# MCU_CLOCK_AND_USER_INTERFACE.net
KiCad netlist of a schematic drawn in Altium Designer
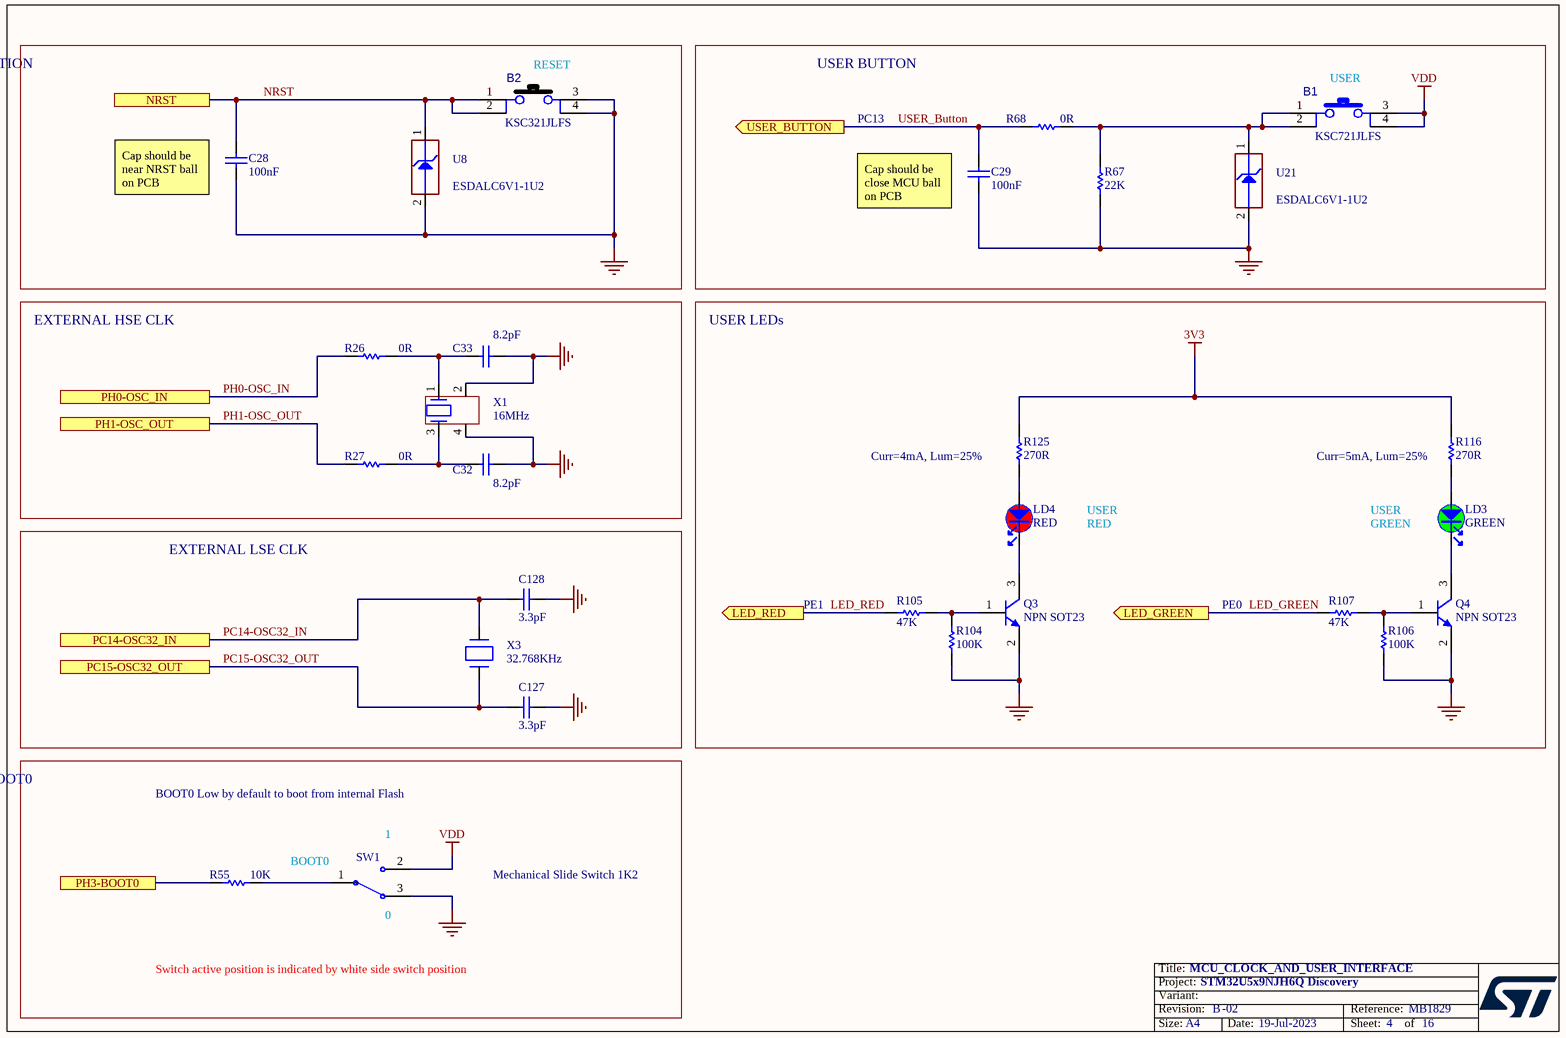
[diagram p0: MCU_CLOCK_AND_USER_INTERFACE.SchDoc]

(export (version "E")
  (design (tool "Eeschema 10.0.6"))
  (components
    (comp (ref "B1")
      (value "KSC721JLFS")
      (footprint "MCD_PARTS:SWI_C&K_KSC721JLFS_BLUE")
      (description "Switch HW BLUE High4.3mm 2.25 Newtons, BEND type")
      (fields (field (name "INTERNAL_PART_NUMBER") "MCD-01800") (field (name "MANUFACTURER") "C&K"))
      (libsource (lib "MCD_PARTS_database") (part "SW_BLUE_KSC721JLFS"))
    )
    (comp (ref "B2")
      (value "KSC321JLFS")
      (footprint "MCD_PARTS:SWI_C&K_KSC321JLFS_BLACK")
      (description "Switch HW BLACK High3.5mm 2Newtons, BEND type")
      (fields (field (name "INTERNAL_PART_NUMBER") "MCD-01799") (field (name "MANUFACTURER") "C&K"))
      (libsource (lib "MCD_PARTS_database") (part "SW_BLACK_KSC321JLFS"))
    )
    (comp (ref "C28")
      (value "100nF")
      (footprint "MCD_PARTS:C0402")
      (description "Capacitor, MLCC, 100nF, 16V, X7R, +/-10%, 0402, T=0.5mm")
      (fields
        (field (name "INTERNAL_PART_NUMBER") "MCD-00006")
        (field (name "MANUFACTURER_PART_NUMBER") "CC0402KRX7R7BB104")
      )
      (libsource (lib "MCD_PARTS_database") (part "Capacitor"))
    )
    (comp (ref "C29")
      (value "100nF")
      (footprint "MCD_PARTS:C0402")
      (description "Capacitor, MLCC, 100nF, 16V, X7R, +/-10%, 0402, T=0.5mm")
      (fields
        (field (name "INTERNAL_PART_NUMBER") "MCD-00006")
        (field (name "MANUFACTURER_PART_NUMBER") "CC0402KRX7R7BB104")
      )
      (libsource (lib "MCD_PARTS_database") (part "Capacitor"))
    )
    (comp (ref "C32")
      (value "8.2pF")
      (footprint "MCD_PARTS:C0402")
      (description "Capacitor, MLCC, 8.2pF, 50V, NPO, +/-0.25pF, 0402, T=0.5mm")
      (fields (field (name "INTERNAL_PART_NUMBER") "MCD-01932") (field (name "MANUFACTURER") "YAGEO"))
      (libsource (lib "MCD_PARTS_database") (part "Capacitor"))
    )
    (comp (ref "C33")
      (value "8.2pF")
      (footprint "MCD_PARTS:C0402")
      (description "Capacitor, MLCC, 8.2pF, 50V, NPO, +/-0.25pF, 0402, T=0.5mm")
      (fields (field (name "INTERNAL_PART_NUMBER") "MCD-01932") (field (name "MANUFACTURER") "YAGEO"))
      (libsource (lib "MCD_PARTS_database") (part "Capacitor"))
    )
    (comp (ref "C127")
      (value "3.3pF")
      (footprint "MCD_PARTS:C0402")
      (description "Capacitor, MLCC, 3.3pF, 50V, NPO, +/-0.1pF, 0402, T=0.5mm")
      (fields (field (name "INTERNAL_PART_NUMBER") "MCD-01775") (field (name "MANUFACTURER") "YAGEO"))
      (libsource (lib "MCD_PARTS_database") (part "Capacitor"))
    )
    (comp (ref "C128")
      (value "3.3pF")
      (footprint "MCD_PARTS:C0402")
      (description "Capacitor, MLCC, 3.3pF, 50V, NPO, +/-0.1pF, 0402, T=0.5mm")
      (fields (field (name "INTERNAL_PART_NUMBER") "MCD-01775") (field (name "MANUFACTURER") "YAGEO"))
      (libsource (lib "MCD_PARTS_database") (part "Capacitor"))
    )
    (comp (ref "LD3")
      (value "GREEN")
      (footprint "MCD_PARTS:LED_0603_OSRAM_LG-Q396-PS-35_GREEN_1A2K_H0P4")
      (description "LED Green, 0603 SMD, Forward Voltage Typ=2V, Max=2.5V")
      (fields
        (field (name "INTERNAL_PART_NUMBER") "MCD-00588")
        (field (name "MANUFACTURER_PART_NUMBER") "LG Q396-PS-35")
      )
      (libsource (lib "MCD_PARTS_database") (part "LED_green"))
    )
    (comp (ref "LD4")
      (value "RED")
      (footprint "MCD_PARTS:LED_0603_OSRAM_LS-Q976-NR-1_RED_1A2K_H0P8")
      (description "LED Red, 0603 SMD, Forward Voltage Typ=2V, Max=2.5V")
      (fields
        (field (name "INTERNAL_PART_NUMBER") "MCD-00586")
        (field (name "MANUFACTURER_PART_NUMBER") "LS Q976-NR-1")
      )
      (libsource (lib "MCD_PARTS_database") (part "LED_red"))
    )
    (comp (ref "Q3")
      (value "NPN SOT23")
      (footprint "MCD_PARTS:NPN_SOT23")
      (description "NPN Bipolar Transistor")
      (fields
        (field (name "INTERNAL_PART_NUMBER") "MCD-00073")
        (field (name "MANUFACTURER_PART_NUMBER") "BSR14")
      )
      (libsource (lib "MCD_PARTS_database") (part "9013-SOT23"))
    )
    (comp (ref "Q4")
      (value "NPN SOT23")
      (footprint "MCD_PARTS:NPN_SOT23")
      (description "NPN Bipolar Transistor")
      (fields
        (field (name "INTERNAL_PART_NUMBER") "MCD-00073")
        (field (name "MANUFACTURER_PART_NUMBER") "BSR14")
      )
      (libsource (lib "MCD_PARTS_database") (part "9013-SOT23"))
    )
    (comp (ref "R26")
      (value "0R")
      (footprint "MCD_PARTS:R0402")
      (description "Resistor, 0R, 0402, +/-5%, 1/16W")
      (fields
        (field (name "INTERNAL_PART_NUMBER") "MCD-00052")
        (field (name "MANUFACTURER_PART_NUMBER") "RC0402JR-070RL")
      )
      (libsource (lib "MCD_PARTS_database") (part "Resistor"))
    )
    (comp (ref "R27")
      (value "0R")
      (footprint "MCD_PARTS:R0402")
      (description "Resistor, 0R, 0402, +/-5%, 1/16W")
      (fields
        (field (name "INTERNAL_PART_NUMBER") "MCD-00052")
        (field (name "MANUFACTURER_PART_NUMBER") "RC0402JR-070RL")
      )
      (libsource (lib "MCD_PARTS_database") (part "Resistor"))
    )
    (comp (ref "R55")
      (value "10K")
      (footprint "MCD_PARTS:R0603")
      (description "Resistor, 10K, 0603, +/-1%, 1/10W")
      (fields
        (field (name "INTERNAL_PART_NUMBER") "MCD-00220")
        (field (name "MANUFACTURER_PART_NUMBER") "RC0603FR-0710KL")
      )
      (libsource (lib "MCD_PARTS_database") (part "Resistor"))
    )
    (comp (ref "R67")
      (value "22K")
      (footprint "MCD_PARTS:R0603")
      (description "Resistor, 22K, 0603, +/-1%, 1/10W")
      (fields
        (field (name "INTERNAL_PART_NUMBER") "MCD-00430")
        (field (name "MANUFACTURER_PART_NUMBER") "RC0603FR-0722KL")
      )
      (libsource (lib "MCD_PARTS_database") (part "Resistor"))
    )
    (comp (ref "R68")
      (value "0R")
      (footprint "MCD_PARTS:R0603")
      (description "Resistor, 0R, 0603, +/-5%, 1/10W")
      (fields
        (field (name "INTERNAL_PART_NUMBER") "MCD-00056")
        (field (name "MANUFACTURER_PART_NUMBER") "RC0603JR-070RL")
      )
      (libsource (lib "MCD_PARTS_database") (part "Resistor"))
    )
    (comp (ref "R104")
      (value "100K")
      (footprint "MCD_PARTS:R0603")
      (description "Resistor, 100K, 0603, +/- 1%, 1/10W")
      (fields
        (field (name "INTERNAL_PART_NUMBER") "MCD-00223")
        (field (name "MANUFACTURER_PART_NUMBER") "RC0603FR-07100KL")
      )
      (libsource (lib "MCD_PARTS_database") (part "Resistor"))
    )
    (comp (ref "R105")
      (value "47K")
      (footprint "MCD_PARTS:R0603")
      (description "Resistor, 47K, 0603, 1%, 1/10W")
      (fields
        (field (name "INTERNAL_PART_NUMBER") "MCD-00222")
        (field (name "MANUFACTURER_PART_NUMBER") "RC0603FR-0747KL")
      )
      (libsource (lib "MCD_PARTS_database") (part "Resistor"))
    )
    (comp (ref "R106")
      (value "100K")
      (footprint "MCD_PARTS:R0603")
      (description "Resistor, 100K, 0603, +/- 1%, 1/10W")
      (fields
        (field (name "INTERNAL_PART_NUMBER") "MCD-00223")
        (field (name "MANUFACTURER_PART_NUMBER") "RC0603FR-07100KL")
      )
      (libsource (lib "MCD_PARTS_database") (part "Resistor"))
    )
    (comp (ref "R107")
      (value "47K")
      (footprint "MCD_PARTS:R0603")
      (description "Resistor, 47K, 0603, 1%, 1/10W")
      (fields
        (field (name "INTERNAL_PART_NUMBER") "MCD-00222")
        (field (name "MANUFACTURER_PART_NUMBER") "RC0603FR-0747KL")
      )
      (libsource (lib "MCD_PARTS_database") (part "Resistor"))
    )
    (comp (ref "R116")
      (value "270R")
      (footprint "MCD_PARTS:R0402")
      (description "Resistor, 270R, 0402, +/-1%, 1/16W")
      (fields (field (name "INTERNAL_PART_NUMBER") "MCD-00441") (field (name "MANUFACTURER") "YAGEO"))
      (libsource (lib "MCD_PARTS_database") (part "Resistor"))
    )
    (comp (ref "R125")
      (value "270R")
      (footprint "MCD_PARTS:R0402")
      (description "Resistor, 270R, 0402, +/-1%, 1/16W")
      (fields
        (field (name "INTERNAL_PART_NUMBER") "MCD-00441")
        (field (name "MANUFACTURER_PART_NUMBER") "RC0402FR-07270RL")
      )
      (libsource (lib "MCD_PARTS_database") (part "Resistor"))
    )
    (comp (ref "SW1")
      (value "Mechanical Slide Switch 1K2")
      (footprint "MCD_PARTS:SWI_EAO_09-03290-01_EXTENDED_STRAIGHT_BLACK")
      (description "Mechanical Slide Switches 1K2 BLK ACT GOLD STRT MNT")
      (fields (field (name "INTERNAL_PART_NUMBER") "MCD-00566") (field (name "MANUFACTURER") "EAO"))
      (libsource (lib "MCD_PARTS_database") (part "SW_MECA_1K2"))
    )
    (comp (ref "U8")
      (value "ESDALC6V1-1U2")
      (footprint "MCD_PARTS:ESD_ST0201")
      (description "ESD protection 6V1")
      (fields
        (field (name "INTERNAL_PART_NUMBER") "MCD-00170")
        (field (name "MANUFACTURER") "STMICROELECTRONICS")
      )
      (libsource (lib "MCD_PARTS_database") (part "ESD-TRANSIL"))
    )
    (comp (ref "U21")
      (value "ESDALC6V1-1U2")
      (footprint "MCD_PARTS:ESD_ST0201")
      (description "ESD protection 6V1")
      (fields
        (field (name "INTERNAL_PART_NUMBER") "MCD-00170")
        (field (name "MANUFACTURER") "STMICROELECTRONICS")
      )
      (libsource (lib "MCD_PARTS_database") (part "ESD-TRANSIL"))
    )
    (comp (ref "X1")
      (value "16MHz")
      (footprint "MCD_PARTS:CRY_NX2016SA_4P")
      (description "Crystal, 16 MHz, 8pF, +/-20ppm, 200R, 2x1.6mm")
      (fields
        (field (name "INTERNAL_PART_NUMBER") "MCD-01476")
        (field (name "MANUFACTURER_PART_NUMBER") "NX2016SA-16MHZ-EXS00A-CS07826")
      )
      (libsource (lib "MCD_PARTS_database") (part "XTAL_4_PINS"))
    )
    (comp (ref "X3")
      (value "32.768KHz")
      (footprint "MCD_PARTS:CRY_NX2012SA_2P")
      (description "Crystal, 32.768kHz, 6pF, +/-20ppm, 80K, 2.05x1.2mm")
      (fields
        (field (name "INTERNAL_PART_NUMBER") "MCD-01479")
        (field (name "MANUFACTURER_PART_NUMBER") "NX2012SA-32.768KHZ-EXS00A-MU00527")
      )
      (libsource (lib "MCD_PARTS_database") (part "XTAL_2_PINS"))
    )
  )
  (nets
    (net (code "1") (name "/LED_GREEN") (class "Default")
      (node (ref "R107") (pin "1") (pinfunction "1_1") (pintype "passive"))
    )
    (net (code "2") (name "/LED_RED") (class "Default")
      (node (ref "R105") (pin "1") (pinfunction "1_1") (pintype "passive"))
    )
    (net (code "3") (name "/NRST") (class "Default")
      (node (ref "B2") (pin "1") (pinfunction "1_1") (pintype "passive"))
      (node (ref "B2") (pin "2") (pinfunction "2_2") (pintype "passive"))
      (node (ref "C28") (pin "2") (pinfunction "2_2") (pintype "passive"))
      (node (ref "U8") (pin "1") (pinfunction "IO1_1") (pintype "passive"))
    )
    (net (code "4") (name "/PC14-OSC32_IN") (class "Default")
      (node (ref "C128") (pin "1") (pinfunction "1_1") (pintype "passive"))
      (node (ref "X3") (pin "2") (pinfunction "X2_2") (pintype "passive"))
    )
    (net (code "5") (name "/PC15-OSC32_OUT") (class "Default")
      (node (ref "C127") (pin "1") (pinfunction "1_1") (pintype "passive"))
      (node (ref "X3") (pin "1") (pinfunction "X1_1") (pintype "passive"))
    )
    (net (code "6") (name "/PH0-OSC_IN") (class "Default")
      (node (ref "R26") (pin "1") (pinfunction "1_1") (pintype "passive"))
    )
    (net (code "7") (name "/PH1-OSC_OUT") (class "Default")
      (node (ref "R27") (pin "1") (pinfunction "1_1") (pintype "passive"))
    )
    (net (code "8") (name "/PH3-BOOT0") (class "Default")
      (node (ref "R55") (pin "1") (pinfunction "1_1") (pintype "passive"))
    )
    (net (code "9") (name "/USER_Button") (class "Default")
      (node (ref "C29") (pin "2") (pinfunction "2_2") (pintype "passive"))
      (node (ref "R68") (pin "1") (pinfunction "1_1") (pintype "passive"))
    )
    (net (code "10") (name "3V3") (class "Default")
      (node (ref "R116") (pin "2") (pinfunction "2_2") (pintype "passive"))
      (node (ref "R125") (pin "2") (pinfunction "2_2") (pintype "passive"))
    )
    (net (code "11") (name "GND") (class "Default")
      (node (ref "B2") (pin "3") (pinfunction "3_3") (pintype "passive"))
      (node (ref "B2") (pin "4") (pinfunction "4_4") (pintype "passive"))
      (node (ref "C127") (pin "2") (pinfunction "2_2") (pintype "passive"))
      (node (ref "C128") (pin "2") (pinfunction "2_2") (pintype "passive"))
      (node (ref "C28") (pin "1") (pinfunction "1_1") (pintype "passive"))
      (node (ref "C29") (pin "1") (pinfunction "1_1") (pintype "passive"))
      (node (ref "C32") (pin "2") (pinfunction "2_2") (pintype "passive"))
      (node (ref "C33") (pin "2") (pinfunction "2_2") (pintype "passive"))
      (node (ref "Q3") (pin "2") (pinfunction "E_2") (pintype "passive"))
      (node (ref "Q4") (pin "2") (pinfunction "E_2") (pintype "passive"))
      (node (ref "R104") (pin "1") (pinfunction "1_1") (pintype "passive"))
      (node (ref "R106") (pin "1") (pinfunction "1_1") (pintype "passive"))
      (node (ref "R67") (pin "1") (pinfunction "1_1") (pintype "passive"))
      (node (ref "SW1") (pin "3") (pinfunction "3_3") (pintype "passive"))
      (node (ref "U21") (pin "2") (pinfunction "GND_2") (pintype "passive"))
      (node (ref "U8") (pin "2") (pinfunction "GND_2") (pintype "passive"))
      (node (ref "X1") (pin "2") (pinfunction "2_2") (pintype "passive"))
      (node (ref "X1") (pin "4") (pinfunction "4_4") (pintype "passive"))
    )
    (net (code "12") (name "Net-(C32-Pad1)") (class "Default")
      (node (ref "C32") (pin "1") (pinfunction "1_1") (pintype "passive"))
      (node (ref "R27") (pin "2") (pinfunction "2_2") (pintype "passive"))
      (node (ref "X1") (pin "3") (pinfunction "3_3") (pintype "passive"))
    )
    (net (code "13") (name "Net-(C33-Pad1)") (class "Default")
      (node (ref "C33") (pin "1") (pinfunction "1_1") (pintype "passive"))
      (node (ref "R26") (pin "2") (pinfunction "2_2") (pintype "passive"))
      (node (ref "X1") (pin "1") (pinfunction "1_1") (pintype "passive"))
    )
    (net (code "14") (name "Net-(LD3-Pad1)") (class "Default")
      (node (ref "LD3") (pin "1") (pintype "passive"))
      (node (ref "R116") (pin "1") (pinfunction "1_1") (pintype "passive"))
    )
    (net (code "15") (name "Net-(LD4-Pad1)") (class "Default")
      (node (ref "LD4") (pin "1") (pintype "passive"))
      (node (ref "R125") (pin "1") (pinfunction "1_1") (pintype "passive"))
    )
    (net (code "16") (name "Net-(Q3-B)") (class "Default")
      (node (ref "Q3") (pin "1") (pinfunction "B_1") (pintype "passive"))
      (node (ref "R104") (pin "2") (pinfunction "2_2") (pintype "passive"))
      (node (ref "R105") (pin "2") (pinfunction "2_2") (pintype "passive"))
    )
    (net (code "17") (name "Net-(Q3-C)") (class "Default")
      (node (ref "LD4") (pin "2") (pintype "passive"))
      (node (ref "Q3") (pin "3") (pinfunction "C_3") (pintype "passive"))
    )
    (net (code "18") (name "Net-(Q4-B)") (class "Default")
      (node (ref "Q4") (pin "1") (pinfunction "B_1") (pintype "passive"))
      (node (ref "R106") (pin "2") (pinfunction "2_2") (pintype "passive"))
      (node (ref "R107") (pin "2") (pinfunction "2_2") (pintype "passive"))
    )
    (net (code "19") (name "Net-(Q4-C)") (class "Default")
      (node (ref "LD3") (pin "2") (pintype "passive"))
      (node (ref "Q4") (pin "3") (pinfunction "C_3") (pintype "passive"))
    )
    (net (code "20") (name "Net-(R55-Pad2)") (class "Default")
      (node (ref "R55") (pin "2") (pinfunction "2_2") (pintype "passive"))
      (node (ref "SW1") (pin "1") (pinfunction "1_1") (pintype "passive"))
    )
    (net (code "21") (name "Net-(U21-IO1)") (class "Default")
      (node (ref "B1") (pin "1") (pinfunction "1_1") (pintype "passive"))
      (node (ref "B1") (pin "2") (pinfunction "2_2") (pintype "passive"))
      (node (ref "R67") (pin "2") (pinfunction "2_2") (pintype "passive"))
      (node (ref "R68") (pin "2") (pinfunction "2_2") (pintype "passive"))
      (node (ref "U21") (pin "1") (pinfunction "IO1_1") (pintype "passive"))
    )
    (net (code "22") (name "VDD") (class "Default")
      (node (ref "B1") (pin "3") (pinfunction "3_3") (pintype "passive"))
      (node (ref "B1") (pin "4") (pinfunction "4_4") (pintype "passive"))
      (node (ref "SW1") (pin "2") (pinfunction "2_2") (pintype "passive"))
    )
  )
)
